# SCH_-_RC2014-_Dev_V1_1_-_freeroute.net
KiCad netlist of a schematic drawn in EasyEDA
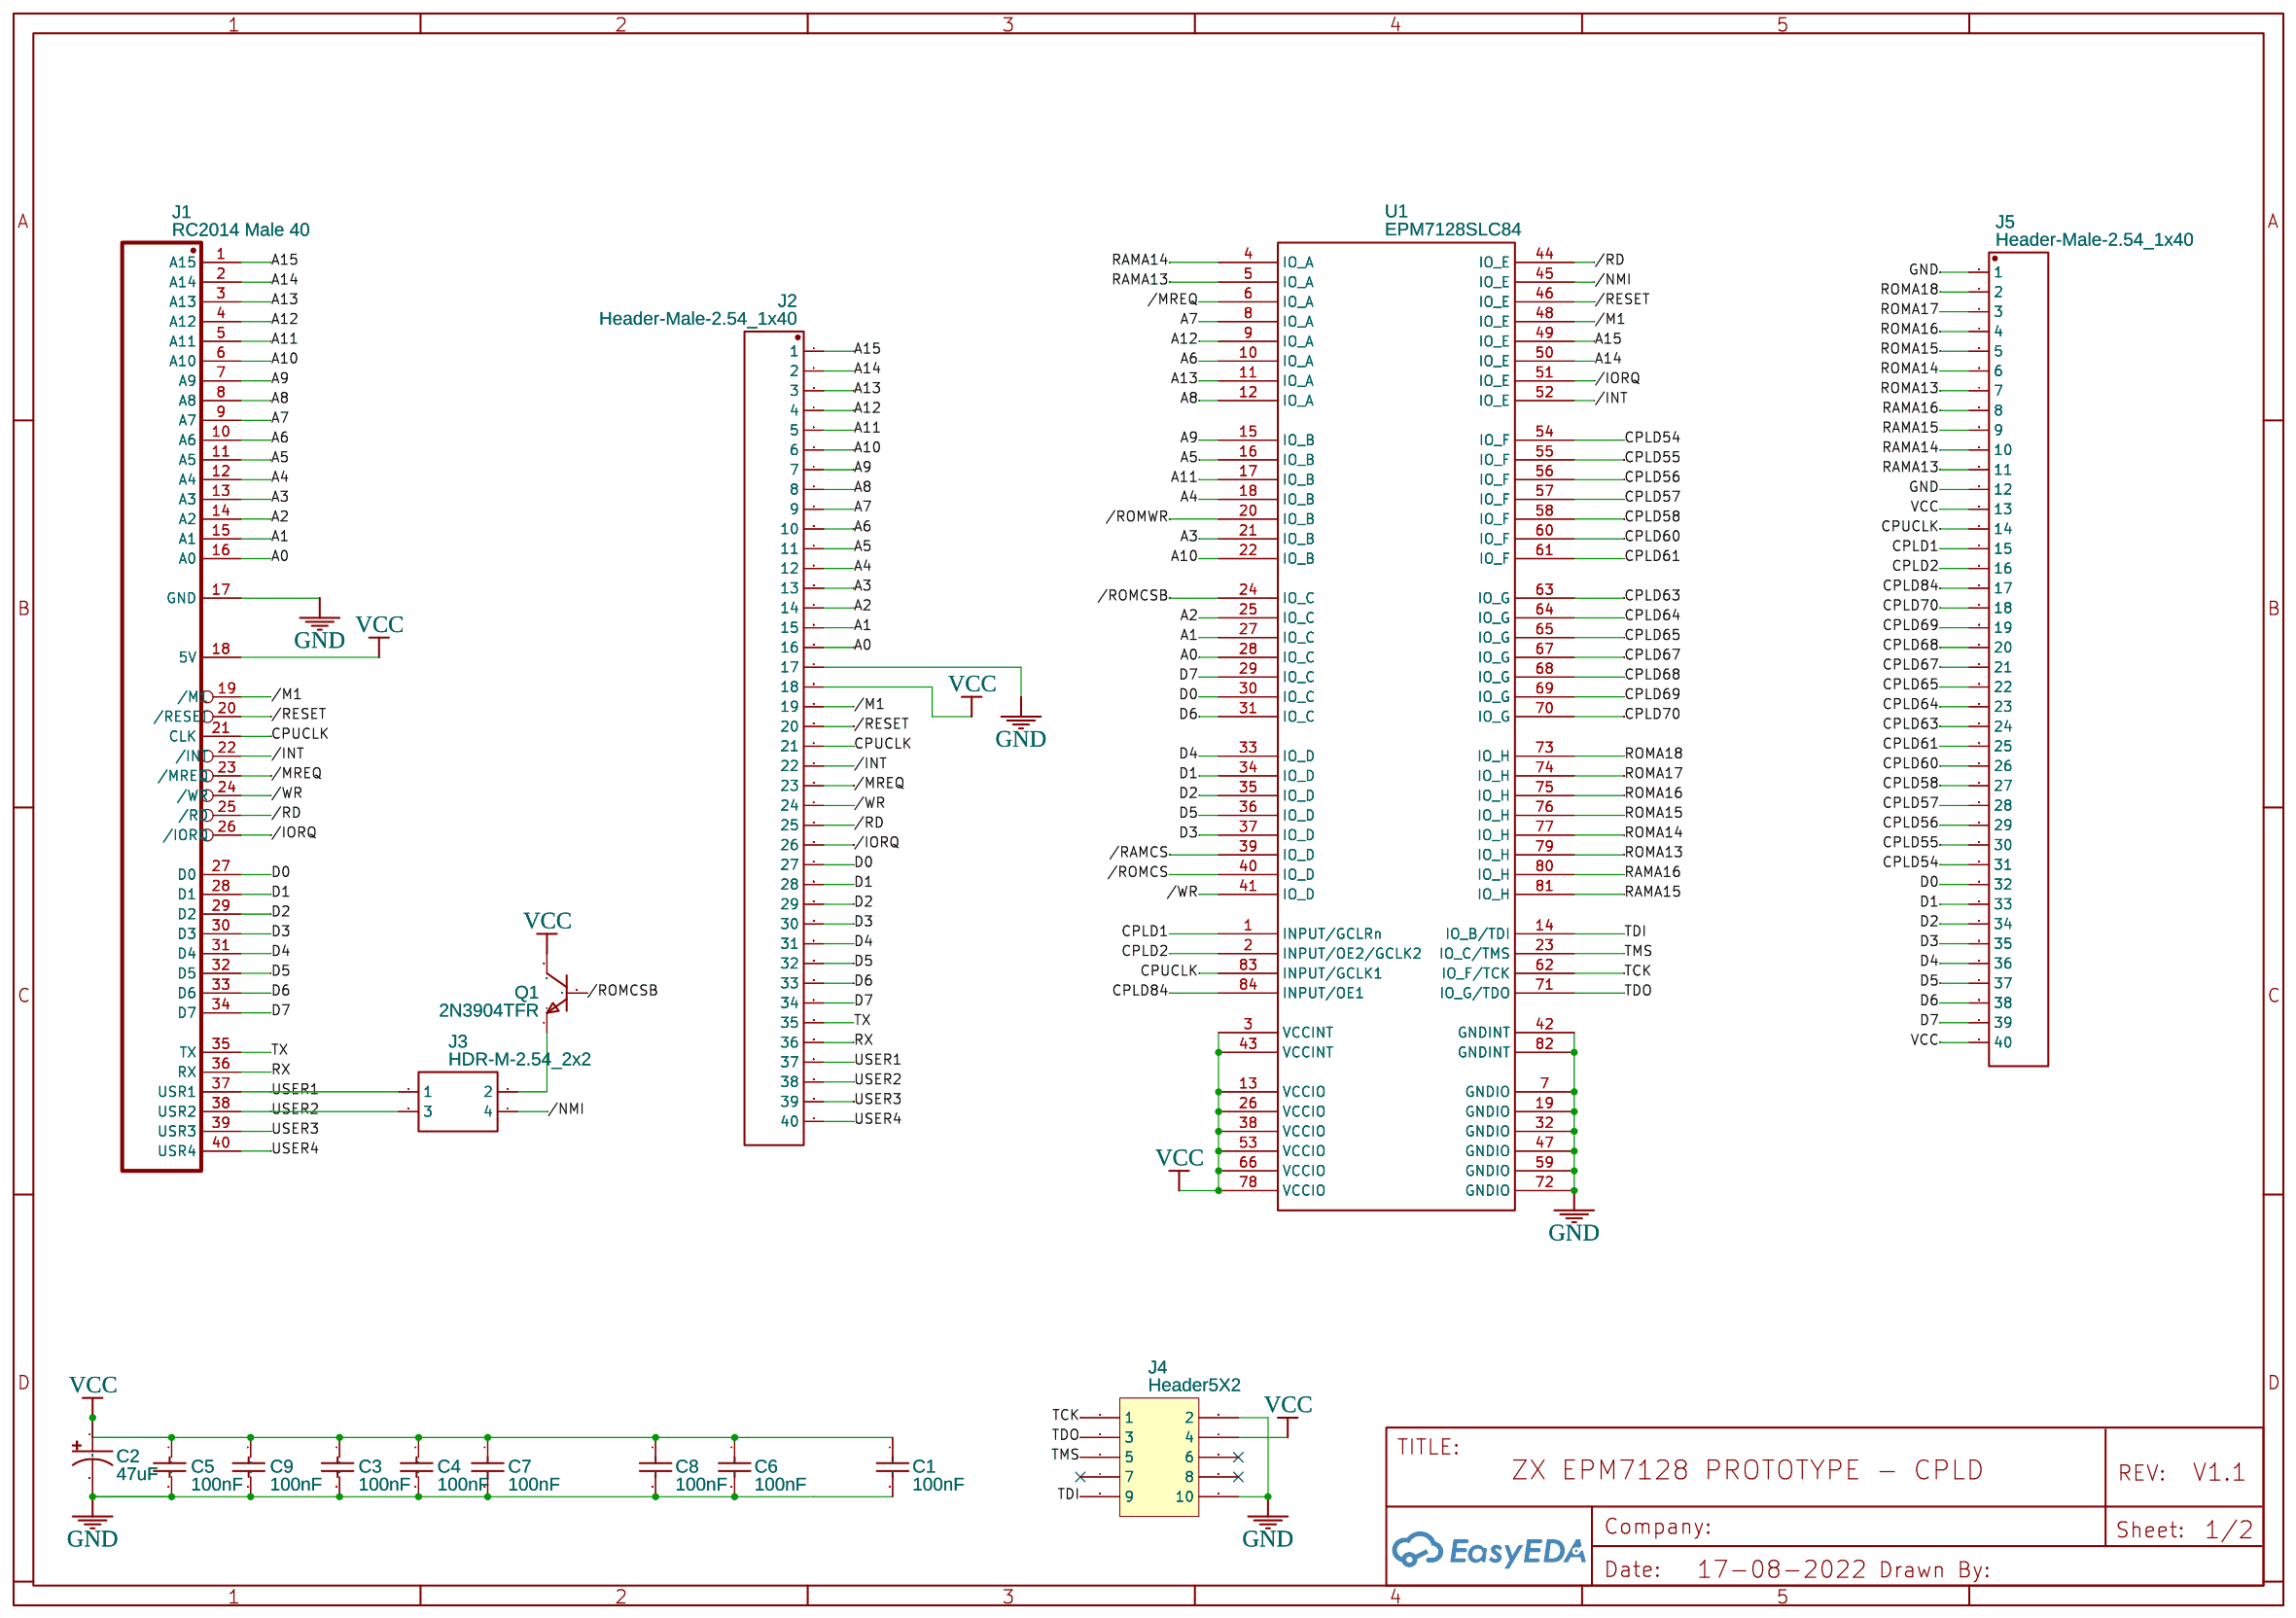
[diagram p0: SCH - RC2014 - Dev V1.1]
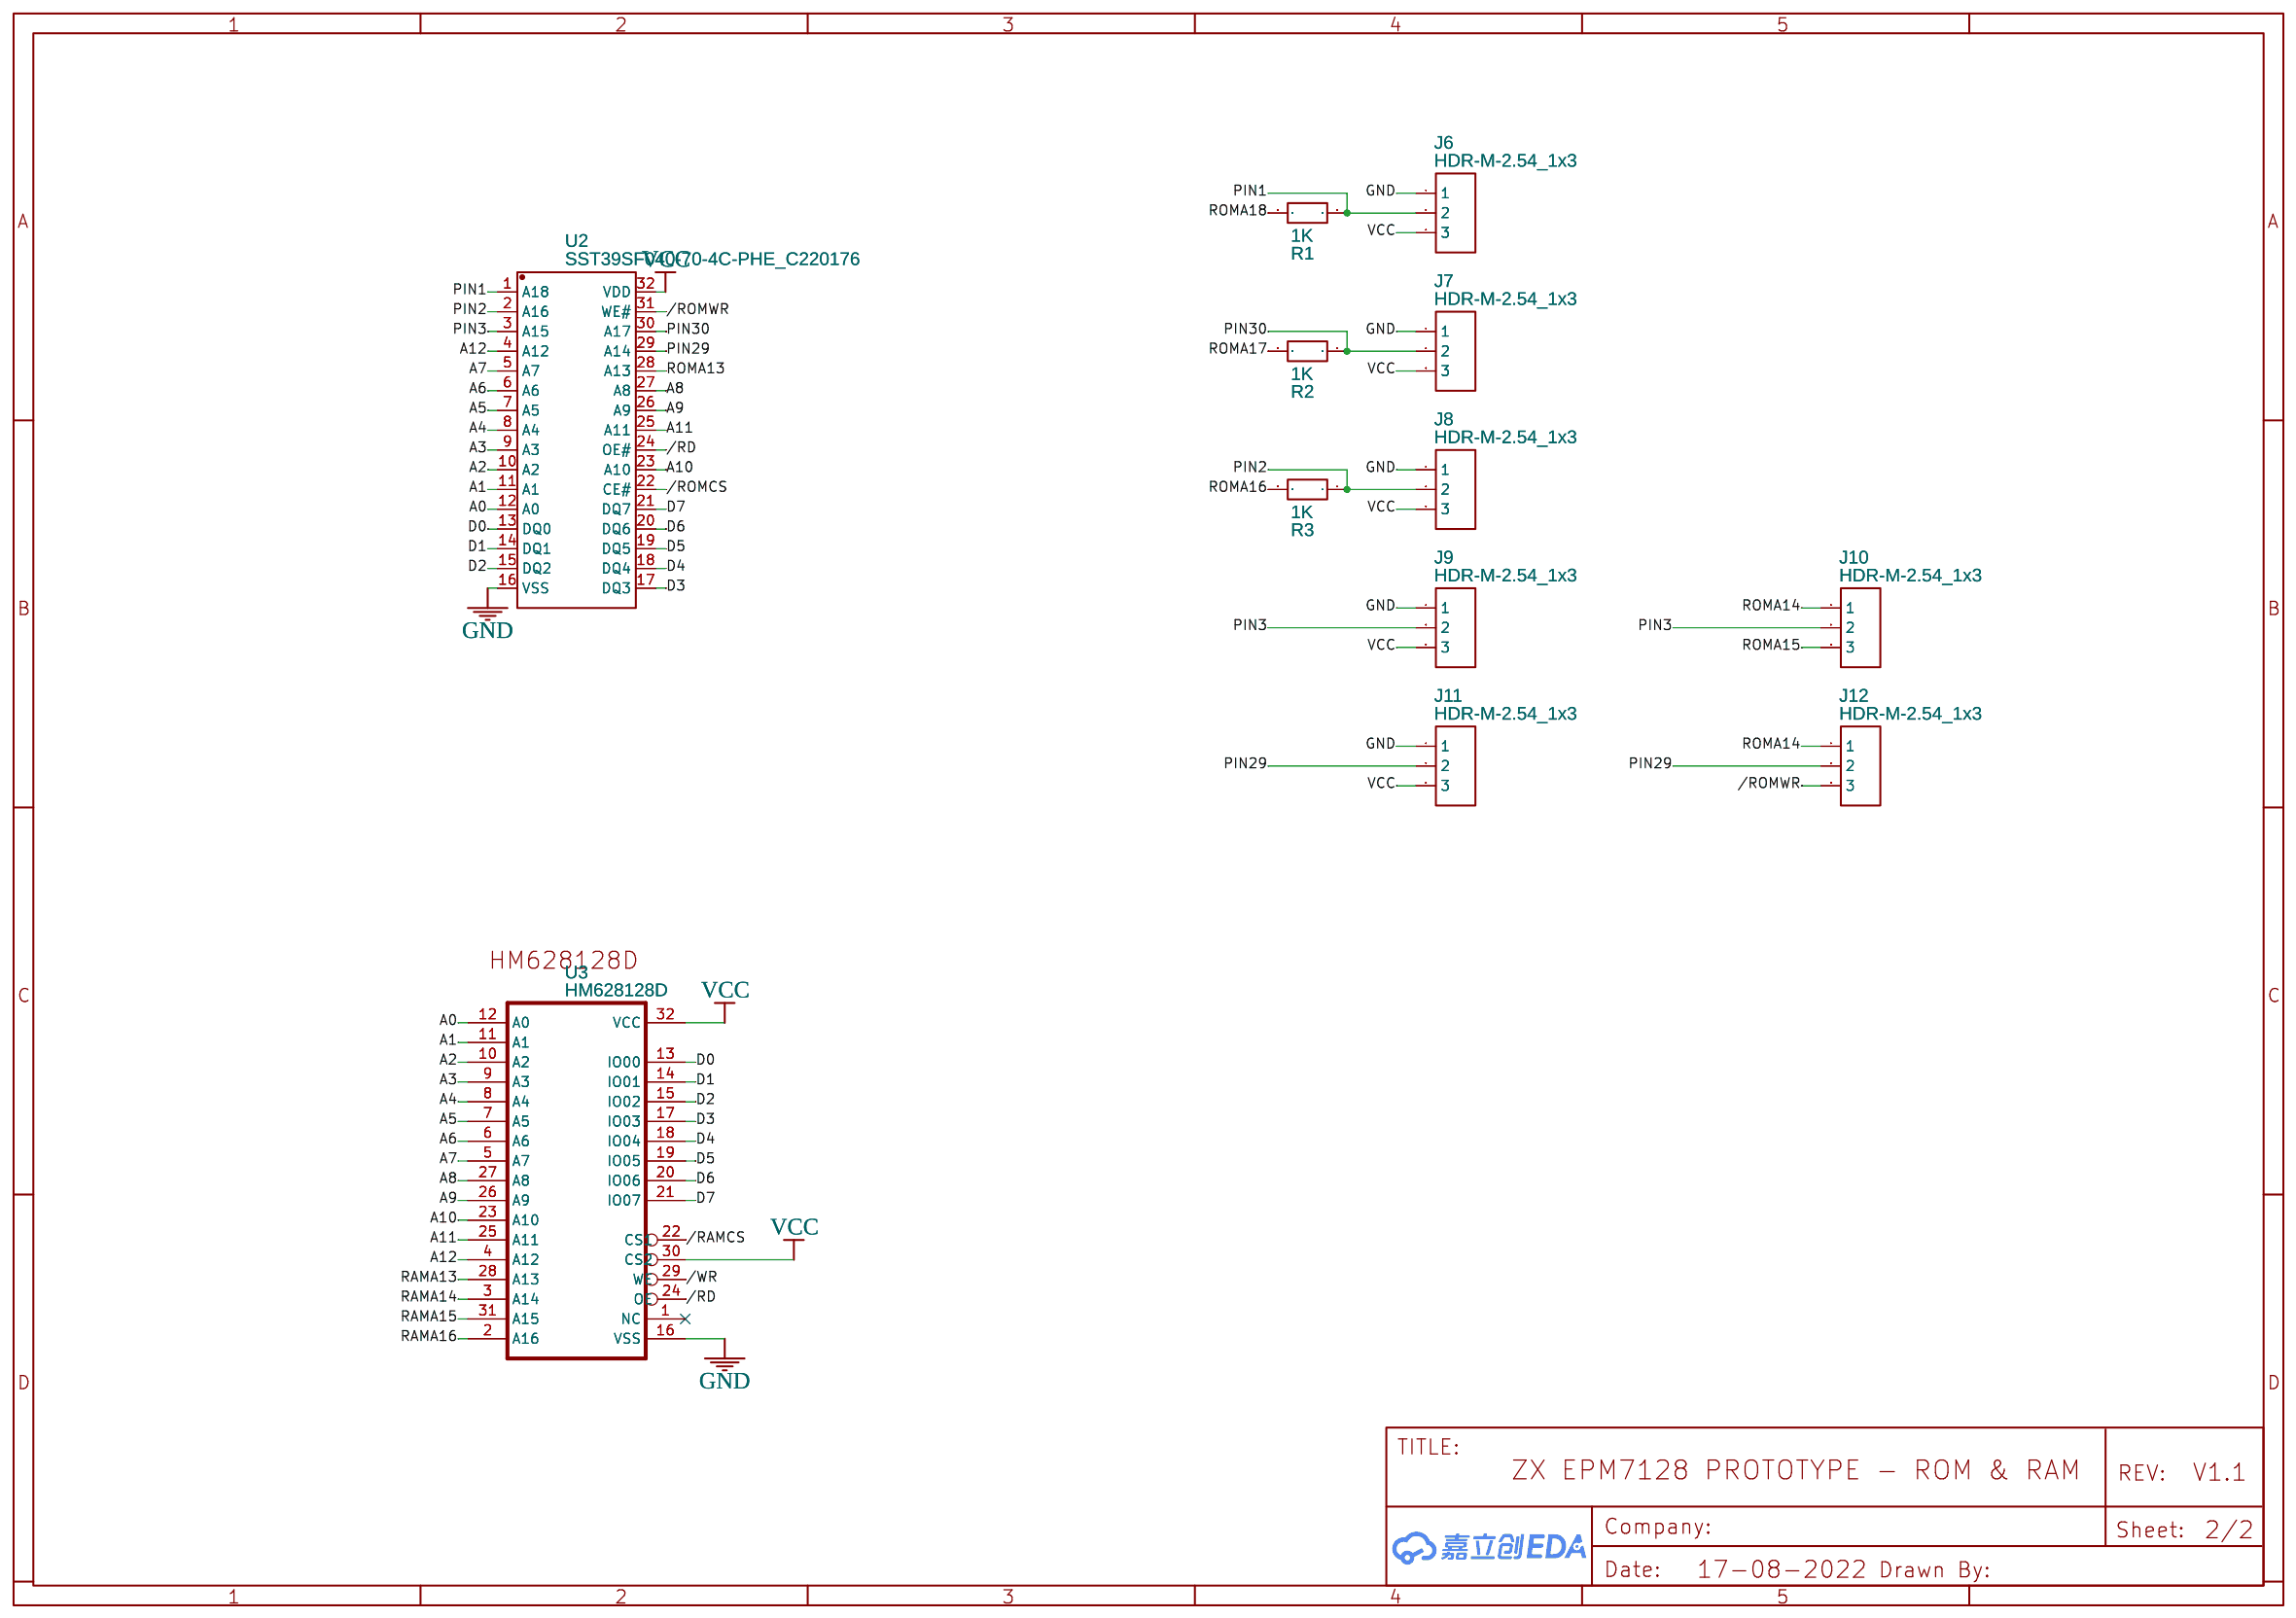
[diagram p1: SCH - ROM & RAM]

(export (version "E")
  (design (tool "Eeschema 10.0.6"))
  (components
    (comp (ref "C1")
      (value "100nF")
      (fields
        (field (name "BOM_Manufacturer Part") "100nF (104) ±20% 100V")
        (field (name "BOM_Supplier Part") "C72322")
      )
      (libsource (lib "") (part "100nF (104) ±20% 100V_1"))
    )
    (comp (ref "C2")
      (value "47uF")
      (fields
        (field (name "BOM_Manufacturer Part") "KM1H470ME110A00CV0")
        (field (name "BOM_Supplier Part") "C190654")
      )
      (libsource (lib "") (part "KM1H470ME110A00CV0"))
    )
    (comp (ref "C3")
      (value "100nF")
      (fields
        (field (name "BOM_Manufacturer Part") "100nF (104) ±20% 100V")
        (field (name "BOM_Supplier Part") "C72322")
      )
      (libsource (lib "") (part "100nF (104) ±20% 100V"))
    )
    (comp (ref "C4")
      (value "100nF")
      (fields
        (field (name "BOM_Manufacturer Part") "100nF (104) ±20% 100V")
        (field (name "BOM_Supplier Part") "C72322")
      )
      (libsource (lib "") (part "100nF (104) ±20% 100V"))
    )
    (comp (ref "C5")
      (value "100nF")
      (fields
        (field (name "BOM_Manufacturer Part") "100nF (104) ±20% 100V")
        (field (name "BOM_Supplier Part") "C72322")
      )
      (libsource (lib "") (part "100nF (104) ±20% 100V"))
    )
    (comp (ref "C6")
      (value "100nF")
      (fields
        (field (name "BOM_Manufacturer Part") "100nF (104) ±20% 100V")
        (field (name "BOM_Supplier Part") "C72322")
      )
      (libsource (lib "") (part "100nF (104) ±20% 100V_1"))
    )
    (comp (ref "C7")
      (value "100nF")
      (fields
        (field (name "BOM_Manufacturer Part") "100nF (104) ±20% 100V")
        (field (name "BOM_Supplier Part") "C72322")
      )
      (libsource (lib "") (part "100nF (104) ±20% 100V_1"))
    )
    (comp (ref "C8")
      (value "100nF")
      (fields
        (field (name "BOM_Manufacturer Part") "100nF (104) ±20% 100V")
        (field (name "BOM_Supplier Part") "C72322")
      )
      (libsource (lib "") (part "100nF (104) ±20% 100V_1"))
    )
    (comp (ref "C9")
      (value "100nF")
      (fields
        (field (name "BOM_Manufacturer Part") "100nF (104) ±20% 100V")
        (field (name "BOM_Supplier Part") "C72322")
      )
      (libsource (lib "") (part "100nF (104) ±20% 100V"))
    )
    (comp (ref "J1") (value "RC2014 Male 40") (libsource (lib "") (part "RC2014 Male 40")))
    (comp (ref "J2")
      (value "Header-Male-2.54_1x40")
      (fields
        (field (name "BOM_Manufacturer Part") "2.54mm 1x40P")
        (field (name "BOM_Supplier Part") "C2337")
      )
      (libsource (lib "") (part "Header-Male-2.54_1x40_1"))
    )
    (comp (ref "J3")
      (value "HDR-M-2.54_2x2")
      (fields (field (name "BOM_Supplier Part") "C66690"))
      (libsource (lib "") (part "HDR-M-2.54_2x2"))
    )
    (comp (ref "J4")
      (value "Header5X2")
      (fields
        (field (name "BOM_Manufacturer Part") "SBH11-PBPC-D05-ST-BK")
        (field (name "BOM_Supplier Part") "S9169-ND")
      )
      (libsource (lib "") (part "Header5X2"))
    )
    (comp (ref "J5")
      (value "Header-Male-2.54_1x40")
      (fields
        (field (name "BOM_Manufacturer Part") "2.54mm 1x40P")
        (field (name "BOM_Supplier Part") "C2337")
      )
      (libsource (lib "") (part "Header-Male-2.54_1x40"))
    )
    (comp (ref "Q1")
      (value "2N3904TFR")
      (fields (field (name "BOM_Supplier Part") "C258185"))
      (libsource (lib "") (part "2N3904TFR"))
    )
    (comp (ref "U1")
      (value "EPM7128SLC84")
      (fields (field (name "BOM_Supplier Part") "692-Z8S18020VEG"))
      (libsource (lib "") (part "EPM7128SLC84"))
    )
    (comp (ref "J6")
      (value "HDR-M-2.54_1x3")
      (fields (field (name "BOM_Supplier Part") "C180248"))
      (libsource (lib "") (part "HDR-M-2.54_1x3"))
    )
    (comp (ref "J7")
      (value "HDR-M-2.54_1x3")
      (fields (field (name "BOM_Supplier Part") "C180248"))
      (libsource (lib "") (part "HDR-M-2.54_1x3"))
    )
    (comp (ref "J8")
      (value "HDR-M-2.54_1x3")
      (fields (field (name "BOM_Supplier Part") "C180248"))
      (libsource (lib "") (part "HDR-M-2.54_1x3"))
    )
    (comp (ref "J9")
      (value "HDR-M-2.54_1x3")
      (fields (field (name "BOM_Supplier Part") "C180248"))
      (libsource (lib "") (part "HDR-M-2.54_1x3"))
    )
    (comp (ref "J10")
      (value "HDR-M-2.54_1x3")
      (fields (field (name "BOM_Supplier Part") "C180248"))
      (libsource (lib "") (part "HDR-M-2.54_1x3"))
    )
    (comp (ref "J11")
      (value "HDR-M-2.54_1x3")
      (fields (field (name "BOM_Supplier Part") "C180248"))
      (libsource (lib "") (part "HDR-M-2.54_1x3"))
    )
    (comp (ref "J12")
      (value "HDR-M-2.54_1x3")
      (fields (field (name "BOM_Supplier Part") "C180248"))
      (libsource (lib "") (part "HDR-M-2.54_1x3"))
    )
    (comp (ref "R1") (value "1K") (libsource (lib "") (part "R_AXIAL-0.3_EU")))
    (comp (ref "R2") (value "1K") (libsource (lib "") (part "R_AXIAL-0.3_EU")))
    (comp (ref "R3") (value "1K") (libsource (lib "") (part "R_AXIAL-0.3_EU")))
    (comp (ref "U2")
      (value "SST39SF040-70-4C-PHE_C220176")
      (fields
        (field (name "BOM_Manufacturer Part") "SST39SF040-70-4C-PHE")
        (field (name "BOM_Supplier Part") "C220176")
      )
      (libsource (lib "") (part "SST39SF040-70-4C-PHE_C220176"))
    )
    (comp (ref "U3") (value "HM628128D") (libsource (lib "") (part "HM628128D")))
  )
  (nets
    (net (code "1") (name "A0") (class "Default")
      (node (ref "J1") (pin "16") (pinfunction "A0_16") (pintype "unspecified"))
      (node (ref "J2") (pin "16") (pinfunction "16_16") (pintype "unspecified"))
      (node (ref "U1") (pin "28") (pinfunction "IO_C_28") (pintype "passive"))
      (node (ref "U2") (pin "12") (pinfunction "A0_12") (pintype "unspecified"))
      (node (ref "U3") (pin "12") (pinfunction "A0_12") (pintype "input"))
    )
    (net (code "2") (name "A1") (class "Default")
      (node (ref "J1") (pin "15") (pinfunction "A1_15") (pintype "unspecified"))
      (node (ref "J2") (pin "15") (pinfunction "15_15") (pintype "unspecified"))
      (node (ref "U1") (pin "27") (pinfunction "IO_C_27") (pintype "input"))
      (node (ref "U2") (pin "11") (pinfunction "A1_11") (pintype "unspecified"))
      (node (ref "U3") (pin "11") (pinfunction "A1_11") (pintype "input"))
    )
    (net (code "3") (name "A2") (class "Default")
      (node (ref "J1") (pin "14") (pinfunction "A2_14") (pintype "unspecified"))
      (node (ref "J2") (pin "14") (pinfunction "14_14") (pintype "unspecified"))
      (node (ref "U1") (pin "25") (pinfunction "IO_C_25") (pintype "bidirectional"))
      (node (ref "U2") (pin "10") (pinfunction "A2_10") (pintype "unspecified"))
      (node (ref "U3") (pin "10") (pinfunction "A2_10") (pintype "input"))
    )
    (net (code "4") (name "A3") (class "Default")
      (node (ref "J1") (pin "13") (pinfunction "A3_13") (pintype "unspecified"))
      (node (ref "J2") (pin "13") (pinfunction "13_13") (pintype "unspecified"))
      (node (ref "U1") (pin "21") (pinfunction "IO_B_21") (pintype "bidirectional"))
      (node (ref "U2") (pin "9") (pinfunction "A3_9") (pintype "unspecified"))
      (node (ref "U3") (pin "9") (pinfunction "A3_9") (pintype "input"))
    )
    (net (code "5") (name "A4") (class "Default")
      (node (ref "J1") (pin "12") (pinfunction "A4_12") (pintype "unspecified"))
      (node (ref "J2") (pin "12") (pinfunction "12_12") (pintype "unspecified"))
      (node (ref "U1") (pin "18") (pinfunction "IO_B_18") (pintype "bidirectional"))
      (node (ref "U2") (pin "8") (pinfunction "A4_8") (pintype "unspecified"))
      (node (ref "U3") (pin "8") (pinfunction "A4_8") (pintype "input"))
    )
    (net (code "6") (name "A5") (class "Default")
      (node (ref "J1") (pin "11") (pinfunction "A5_11") (pintype "unspecified"))
      (node (ref "J2") (pin "11") (pinfunction "11_11") (pintype "unspecified"))
      (node (ref "U1") (pin "16") (pinfunction "IO_B_16") (pintype "bidirectional"))
      (node (ref "U2") (pin "7") (pinfunction "A5_7") (pintype "unspecified"))
      (node (ref "U3") (pin "7") (pinfunction "A5_7") (pintype "input"))
    )
    (net (code "7") (name "A6") (class "Default")
      (node (ref "J1") (pin "10") (pinfunction "A6_10") (pintype "unspecified"))
      (node (ref "J2") (pin "10") (pinfunction "10_10") (pintype "unspecified"))
      (node (ref "U1") (pin "10") (pinfunction "IO_A_10") (pintype "bidirectional"))
      (node (ref "U2") (pin "6") (pinfunction "A6_6") (pintype "unspecified"))
      (node (ref "U3") (pin "6") (pinfunction "A6_6") (pintype "input"))
    )
    (net (code "8") (name "A7") (class "Default")
      (node (ref "J1") (pin "9") (pinfunction "A7_9") (pintype "unspecified"))
      (node (ref "J2") (pin "9") (pinfunction "9_9") (pintype "unspecified"))
      (node (ref "U1") (pin "8") (pinfunction "IO_A_8") (pintype "bidirectional"))
      (node (ref "U2") (pin "5") (pinfunction "A7_5") (pintype "unspecified"))
      (node (ref "U3") (pin "5") (pinfunction "A7_5") (pintype "input"))
    )
    (net (code "9") (name "A8") (class "Default")
      (node (ref "J1") (pin "8") (pinfunction "A8_8") (pintype "unspecified"))
      (node (ref "J2") (pin "8") (pinfunction "8_8") (pintype "unspecified"))
      (node (ref "U1") (pin "12") (pinfunction "IO_A_12") (pintype "bidirectional"))
      (node (ref "U2") (pin "27") (pinfunction "A8_27") (pintype "unspecified"))
      (node (ref "U3") (pin "27") (pinfunction "A8_27") (pintype "input"))
    )
    (net (code "10") (name "A9") (class "Default")
      (node (ref "J1") (pin "7") (pinfunction "A9_7") (pintype "unspecified"))
      (node (ref "J2") (pin "7") (pinfunction "7_7") (pintype "unspecified"))
      (node (ref "U1") (pin "15") (pinfunction "IO_B_15") (pintype "bidirectional"))
      (node (ref "U2") (pin "26") (pinfunction "A9_26") (pintype "unspecified"))
      (node (ref "U3") (pin "26") (pinfunction "A9_26") (pintype "input"))
    )
    (net (code "11") (name "A10") (class "Default")
      (node (ref "J1") (pin "6") (pinfunction "A10_6") (pintype "unspecified"))
      (node (ref "J2") (pin "6") (pinfunction "6_6") (pintype "unspecified"))
      (node (ref "U1") (pin "22") (pinfunction "IO_B_22") (pintype "output"))
      (node (ref "U2") (pin "23") (pinfunction "A10_23") (pintype "unspecified"))
      (node (ref "U3") (pin "23") (pinfunction "A10_23") (pintype "input"))
    )
    (net (code "12") (name "A11") (class "Default")
      (node (ref "J1") (pin "5") (pinfunction "A11_5") (pintype "unspecified"))
      (node (ref "J2") (pin "5") (pinfunction "5_5") (pintype "unspecified"))
      (node (ref "U1") (pin "17") (pinfunction "IO_B_17") (pintype "bidirectional"))
      (node (ref "U2") (pin "25") (pinfunction "A11_25") (pintype "unspecified"))
      (node (ref "U3") (pin "25") (pinfunction "A11_25") (pintype "input"))
    )
    (net (code "13") (name "A12") (class "Default")
      (node (ref "J1") (pin "4") (pinfunction "A12_4") (pintype "unspecified"))
      (node (ref "J2") (pin "4") (pinfunction "4_4") (pintype "unspecified"))
      (node (ref "U1") (pin "9") (pinfunction "IO_A_9") (pintype "bidirectional"))
      (node (ref "U2") (pin "4") (pinfunction "A12_4") (pintype "unspecified"))
      (node (ref "U3") (pin "4") (pinfunction "A12_4") (pintype "input"))
    )
    (net (code "14") (name "A13") (class "Default")
      (node (ref "J1") (pin "3") (pinfunction "A13_3") (pintype "unspecified"))
      (node (ref "J2") (pin "3") (pinfunction "3_3") (pintype "unspecified"))
      (node (ref "U1") (pin "11") (pinfunction "IO_A_11") (pintype "bidirectional"))
    )
    (net (code "15") (name "A14") (class "Default")
      (node (ref "J1") (pin "2") (pinfunction "A14_2") (pintype "unspecified"))
      (node (ref "J2") (pin "2") (pinfunction "2_2") (pintype "unspecified"))
      (node (ref "U1") (pin "50") (pinfunction "IO_E_50") (pintype "bidirectional"))
    )
    (net (code "16") (name "A15") (class "Default")
      (node (ref "J1") (pin "1") (pinfunction "A15_1") (pintype "unspecified"))
      (node (ref "J2") (pin "1") (pinfunction "1_1") (pintype "unspecified"))
      (node (ref "U1") (pin "49") (pinfunction "IO_E_49") (pintype "bidirectional"))
    )
    (net (code "17") (name "CPLD1") (class "Default")
      (node (ref "J5") (pin "15") (pinfunction "15_15") (pintype "unspecified"))
      (node (ref "U1") (pin "1") (pinfunction "INPUT/GCLRn_1") (pintype "input"))
    )
    (net (code "18") (name "CPLD2") (class "Default")
      (node (ref "J5") (pin "16") (pinfunction "16_16") (pintype "unspecified"))
      (node (ref "U1") (pin "2") (pinfunction "INPUT/OE2/GCLK2_2") (pintype "input"))
    )
    (net (code "19") (name "CPLD54") (class "Default")
      (node (ref "J5") (pin "31") (pinfunction "31_31") (pintype "unspecified"))
      (node (ref "U1") (pin "54") (pinfunction "IO_F_54") (pintype "bidirectional"))
    )
    (net (code "20") (name "CPLD55") (class "Default")
      (node (ref "J5") (pin "30") (pinfunction "30_30") (pintype "unspecified"))
      (node (ref "U1") (pin "55") (pinfunction "IO_F_55") (pintype "passive"))
    )
    (net (code "21") (name "CPLD56") (class "Default")
      (node (ref "J5") (pin "29") (pinfunction "29_29") (pintype "unspecified"))
      (node (ref "U1") (pin "56") (pinfunction "IO_F_56") (pintype "bidirectional"))
    )
    (net (code "22") (name "CPLD57") (class "Default")
      (node (ref "J5") (pin "28") (pinfunction "28_28") (pintype "unspecified"))
      (node (ref "U1") (pin "57") (pinfunction "IO_F_57") (pintype "bidirectional"))
    )
    (net (code "23") (name "CPLD58") (class "Default")
      (node (ref "J5") (pin "27") (pinfunction "27_27") (pintype "unspecified"))
      (node (ref "U1") (pin "58") (pinfunction "IO_F_58") (pintype "bidirectional"))
    )
    (net (code "24") (name "CPLD60") (class "Default")
      (node (ref "J5") (pin "26") (pinfunction "26_26") (pintype "unspecified"))
      (node (ref "U1") (pin "60") (pinfunction "IO_F_60") (pintype "bidirectional"))
    )
    (net (code "25") (name "CPLD61") (class "Default")
      (node (ref "J5") (pin "25") (pinfunction "25_25") (pintype "unspecified"))
      (node (ref "U1") (pin "61") (pinfunction "IO_F_61") (pintype "bidirectional"))
    )
    (net (code "26") (name "CPLD63") (class "Default")
      (node (ref "J5") (pin "24") (pinfunction "24_24") (pintype "unspecified"))
      (node (ref "U1") (pin "63") (pinfunction "IO_G_63") (pintype "bidirectional"))
    )
    (net (code "27") (name "CPLD64") (class "Default")
      (node (ref "J5") (pin "23") (pinfunction "23_23") (pintype "unspecified"))
      (node (ref "U1") (pin "64") (pinfunction "IO_G_64") (pintype "bidirectional"))
    )
    (net (code "28") (name "CPLD65") (class "Default")
      (node (ref "J5") (pin "22") (pinfunction "22_22") (pintype "unspecified"))
      (node (ref "U1") (pin "65") (pinfunction "IO_G_65") (pintype "passive"))
    )
    (net (code "29") (name "CPLD67") (class "Default")
      (node (ref "J5") (pin "21") (pinfunction "21_21") (pintype "unspecified"))
      (node (ref "U1") (pin "67") (pinfunction "IO_G_67") (pintype "bidirectional"))
    )
    (net (code "30") (name "CPLD68") (class "Default")
      (node (ref "J5") (pin "20") (pinfunction "20_20") (pintype "unspecified"))
      (node (ref "U1") (pin "68") (pinfunction "IO_G_68") (pintype "bidirectional"))
    )
    (net (code "31") (name "CPLD69") (class "Default")
      (node (ref "J5") (pin "19") (pinfunction "19_19") (pintype "unspecified"))
      (node (ref "U1") (pin "69") (pinfunction "IO_G_69") (pintype "passive"))
    )
    (net (code "32") (name "CPLD70") (class "Default")
      (node (ref "J5") (pin "18") (pinfunction "18_18") (pintype "unspecified"))
      (node (ref "U1") (pin "70") (pinfunction "IO_G_70") (pintype "bidirectional"))
    )
    (net (code "33") (name "CPLD84") (class "Default")
      (node (ref "J5") (pin "17") (pinfunction "17_17") (pintype "unspecified"))
      (node (ref "U1") (pin "84") (pinfunction "INPUT/OE1_84") (pintype "input"))
    )
    (net (code "34") (name "CPUCLK") (class "Default")
      (node (ref "J1") (pin "21") (pinfunction "CLK_21") (pintype "unspecified"))
      (node (ref "J2") (pin "21") (pinfunction "21_21") (pintype "unspecified"))
      (node (ref "J5") (pin "14") (pinfunction "14_14") (pintype "unspecified"))
      (node (ref "U1") (pin "83") (pinfunction "INPUT/GCLK1_83") (pintype "input"))
    )
    (net (code "35") (name "D0") (class "Default")
      (node (ref "J1") (pin "27") (pinfunction "D0_27") (pintype "unspecified"))
      (node (ref "J2") (pin "27") (pinfunction "27_27") (pintype "unspecified"))
      (node (ref "J5") (pin "32") (pinfunction "32_32") (pintype "unspecified"))
      (node (ref "U1") (pin "30") (pinfunction "IO_C_30") (pintype "bidirectional"))
      (node (ref "U2") (pin "13") (pinfunction "DQ0_13") (pintype "unspecified"))
      (node (ref "U3") (pin "13") (pinfunction "IO00_13") (pintype "unspecified"))
    )
    (net (code "36") (name "D1") (class "Default")
      (node (ref "J1") (pin "28") (pinfunction "D1_28") (pintype "unspecified"))
      (node (ref "J2") (pin "28") (pinfunction "28_28") (pintype "unspecified"))
      (node (ref "J5") (pin "33") (pinfunction "33_33") (pintype "unspecified"))
      (node (ref "U1") (pin "34") (pinfunction "IO_D_34") (pintype "input"))
      (node (ref "U2") (pin "14") (pinfunction "DQ1_14") (pintype "unspecified"))
      (node (ref "U3") (pin "14") (pinfunction "IO01_14") (pintype "unspecified"))
    )
    (net (code "37") (name "D2") (class "Default")
      (node (ref "J1") (pin "29") (pinfunction "D2_29") (pintype "unspecified"))
      (node (ref "J2") (pin "29") (pinfunction "29_29") (pintype "unspecified"))
      (node (ref "J5") (pin "34") (pinfunction "34_34") (pintype "unspecified"))
      (node (ref "U1") (pin "35") (pinfunction "IO_D_35") (pintype "input"))
      (node (ref "U2") (pin "15") (pinfunction "DQ2_15") (pintype "unspecified"))
      (node (ref "U3") (pin "15") (pinfunction "IO02_15") (pintype "unspecified"))
    )
    (net (code "38") (name "D3") (class "Default")
      (node (ref "J1") (pin "30") (pinfunction "D3_30") (pintype "unspecified"))
      (node (ref "J2") (pin "30") (pinfunction "30_30") (pintype "unspecified"))
      (node (ref "J5") (pin "35") (pinfunction "35_35") (pintype "unspecified"))
      (node (ref "U1") (pin "37") (pinfunction "IO_D_37") (pintype "bidirectional"))
      (node (ref "U2") (pin "17") (pinfunction "DQ3_17") (pintype "unspecified"))
      (node (ref "U3") (pin "17") (pinfunction "IO03_17") (pintype "unspecified"))
    )
    (net (code "39") (name "D4") (class "Default")
      (node (ref "J1") (pin "31") (pinfunction "D4_31") (pintype "unspecified"))
      (node (ref "J2") (pin "31") (pinfunction "31_31") (pintype "unspecified"))
      (node (ref "J5") (pin "36") (pinfunction "36_36") (pintype "unspecified"))
      (node (ref "U1") (pin "33") (pinfunction "IO_D_33") (pintype "bidirectional"))
      (node (ref "U2") (pin "18") (pinfunction "DQ4_18") (pintype "unspecified"))
      (node (ref "U3") (pin "18") (pinfunction "IO04_18") (pintype "unspecified"))
    )
    (net (code "40") (name "D5") (class "Default")
      (node (ref "J1") (pin "32") (pinfunction "D5_32") (pintype "unspecified"))
      (node (ref "J2") (pin "32") (pinfunction "32_32") (pintype "unspecified"))
      (node (ref "J5") (pin "37") (pinfunction "37_37") (pintype "unspecified"))
      (node (ref "U1") (pin "36") (pinfunction "IO_D_36") (pintype "bidirectional"))
      (node (ref "U2") (pin "19") (pinfunction "DQ5_19") (pintype "unspecified"))
      (node (ref "U3") (pin "19") (pinfunction "IO05_19") (pintype "unspecified"))
    )
    (net (code "41") (name "D6") (class "Default")
      (node (ref "J1") (pin "33") (pinfunction "D6_33") (pintype "unspecified"))
      (node (ref "J2") (pin "33") (pinfunction "33_33") (pintype "unspecified"))
      (node (ref "J5") (pin "38") (pinfunction "38_38") (pintype "unspecified"))
      (node (ref "U1") (pin "31") (pinfunction "IO_C_31") (pintype "passive"))
      (node (ref "U2") (pin "20") (pinfunction "DQ6_20") (pintype "unspecified"))
      (node (ref "U3") (pin "20") (pinfunction "IO06_20") (pintype "unspecified"))
    )
    (net (code "42") (name "D7") (class "Default")
      (node (ref "J1") (pin "34") (pinfunction "D7_34") (pintype "unspecified"))
      (node (ref "J2") (pin "34") (pinfunction "34_34") (pintype "unspecified"))
      (node (ref "J5") (pin "39") (pinfunction "39_39") (pintype "unspecified"))
      (node (ref "U1") (pin "29") (pinfunction "IO_C_29") (pintype "input"))
      (node (ref "U2") (pin "21") (pinfunction "DQ7_21") (pintype "unspecified"))
      (node (ref "U3") (pin "21") (pinfunction "IO07_21") (pintype "unspecified"))
    )
    (net (code "43") (name "GND") (class "Default")
      (node (ref "C1") (pin "2") (pinfunction "2_2") (pintype "input"))
      (node (ref "C2") (pin "2") (pinfunction "2_2") (pintype "unspecified"))
      (node (ref "C3") (pin "2") (pinfunction "2_2") (pintype "input"))
      (node (ref "C4") (pin "2") (pinfunction "2_2") (pintype "input"))
      (node (ref "C5") (pin "2") (pinfunction "2_2") (pintype "input"))
      (node (ref "C6") (pin "2") (pinfunction "2_2") (pintype "input"))
      (node (ref "C7") (pin "2") (pinfunction "2_2") (pintype "input"))
      (node (ref "C8") (pin "2") (pinfunction "2_2") (pintype "input"))
      (node (ref "C9") (pin "2") (pinfunction "2_2") (pintype "input"))
      (node (ref "J1") (pin "17") (pinfunction "GND_17") (pintype "unspecified"))
      (node (ref "J11") (pin "1") (pinfunction "1_1") (pintype "input"))
      (node (ref "J2") (pin "17") (pinfunction "17_17") (pintype "unspecified"))
      (node (ref "J4") (pin "10") (pinfunction "10_10") (pintype "unspecified"))
      (node (ref "J4") (pin "2") (pinfunction "2_2") (pintype "unspecified"))
      (node (ref "J5") (pin "1") (pinfunction "1_1") (pintype "unspecified"))
      (node (ref "J5") (pin "12") (pinfunction "12_12") (pintype "unspecified"))
      (node (ref "J6") (pin "1") (pinfunction "1_1") (pintype "input"))
      (node (ref "J7") (pin "1") (pinfunction "1_1") (pintype "input"))
      (node (ref "J8") (pin "1") (pinfunction "1_1") (pintype "input"))
      (node (ref "J9") (pin "1") (pinfunction "1_1") (pintype "input"))
      (node (ref "U1") (pin "19") (pinfunction "GNDIO_19") (pintype "bidirectional"))
      (node (ref "U1") (pin "32") (pinfunction "GNDIO_32") (pintype "bidirectional"))
      (node (ref "U1") (pin "42") (pinfunction "GNDINT_42") (pintype "input"))
      (node (ref "U1") (pin "47") (pinfunction "GNDIO_47") (pintype "bidirectional"))
      (node (ref "U1") (pin "59") (pinfunction "GNDIO_59") (pintype "bidirectional"))
      (node (ref "U1") (pin "7") (pinfunction "GNDIO_7") (pintype "bidirectional"))
      (node (ref "U1") (pin "72") (pinfunction "GNDIO_72") (pintype "bidirectional"))
      (node (ref "U1") (pin "82") (pinfunction "GNDINT_82") (pintype "input"))
      (node (ref "U2") (pin "16") (pinfunction "VSS_16") (pintype "unspecified"))
      (node (ref "U3") (pin "16") (pinfunction "VSS_16") (pintype "passive"))
    )
    (net (code "44") (name "Net-(Q1-E)") (class "Default")
      (node (ref "J3") (pin "2") (pinfunction "2_2") (pintype "input"))
      (node (ref "Q1") (pin "1") (pinfunction "E_1") (pintype "unspecified"))
    )
    (net (code "45") (name "PIN1") (class "Default")
      (node (ref "J6") (pin "2") (pinfunction "2_2") (pintype "input"))
      (node (ref "R1") (pin "1") (pinfunction "1_1") (pintype "unspecified"))
      (node (ref "U2") (pin "1") (pinfunction "A18_1") (pintype "unspecified"))
    )
    (net (code "46") (name "PIN2") (class "Default")
      (node (ref "J8") (pin "2") (pinfunction "2_2") (pintype "input"))
      (node (ref "R3") (pin "1") (pinfunction "1_1") (pintype "unspecified"))
      (node (ref "U2") (pin "2") (pinfunction "A16_2") (pintype "unspecified"))
    )
    (net (code "47") (name "PIN3") (class "Default")
      (node (ref "J10") (pin "2") (pinfunction "2_2") (pintype "input"))
      (node (ref "J9") (pin "2") (pinfunction "2_2") (pintype "input"))
      (node (ref "U2") (pin "3") (pinfunction "A15_3") (pintype "unspecified"))
    )
    (net (code "48") (name "PIN29") (class "Default")
      (node (ref "J11") (pin "2") (pinfunction "2_2") (pintype "input"))
      (node (ref "J12") (pin "2") (pinfunction "2_2") (pintype "input"))
      (node (ref "U2") (pin "29") (pinfunction "A14_29") (pintype "unspecified"))
    )
    (net (code "49") (name "PIN30") (class "Default")
      (node (ref "J7") (pin "2") (pinfunction "2_2") (pintype "input"))
      (node (ref "R2") (pin "1") (pinfunction "1_1") (pintype "unspecified"))
      (node (ref "U2") (pin "30") (pinfunction "A17_30") (pintype "unspecified"))
    )
    (net (code "50") (name "RAMA13") (class "Default")
      (node (ref "J5") (pin "11") (pinfunction "11_11") (pintype "unspecified"))
      (node (ref "U1") (pin "5") (pinfunction "IO_A_5") (pintype "bidirectional"))
      (node (ref "U3") (pin "28") (pinfunction "A13_28") (pintype "input"))
    )
    (net (code "51") (name "RAMA14") (class "Default")
      (node (ref "J5") (pin "10") (pinfunction "10_10") (pintype "unspecified"))
      (node (ref "U1") (pin "4") (pinfunction "IO_A_4") (pintype "bidirectional"))
      (node (ref "U3") (pin "3") (pinfunction "A14_3") (pintype "input"))
    )
    (net (code "52") (name "RAMA15") (class "Default")
      (node (ref "J5") (pin "9") (pinfunction "9_9") (pintype "unspecified"))
      (node (ref "U1") (pin "81") (pinfunction "IO_H_81") (pintype "bidirectional"))
      (node (ref "U3") (pin "31") (pinfunction "A15_31") (pintype "input"))
    )
    (net (code "53") (name "RAMA16") (class "Default")
      (node (ref "J5") (pin "8") (pinfunction "8_8") (pintype "unspecified"))
      (node (ref "U1") (pin "80") (pinfunction "IO_H_80") (pintype "bidirectional"))
      (node (ref "U3") (pin "2") (pinfunction "A16_2") (pintype "input"))
    )
    (net (code "54") (name "ROMA13") (class "Default")
      (node (ref "J5") (pin "7") (pinfunction "7_7") (pintype "unspecified"))
      (node (ref "U1") (pin "79") (pinfunction "IO_H_79") (pintype "bidirectional"))
      (node (ref "U2") (pin "28") (pinfunction "A13_28") (pintype "unspecified"))
    )
    (net (code "55") (name "ROMA14") (class "Default")
      (node (ref "J10") (pin "1") (pinfunction "1_1") (pintype "input"))
      (node (ref "J12") (pin "1") (pinfunction "1_1") (pintype "input"))
      (node (ref "J5") (pin "6") (pinfunction "6_6") (pintype "unspecified"))
      (node (ref "U1") (pin "77") (pinfunction "IO_H_77") (pintype "bidirectional"))
    )
    (net (code "56") (name "ROMA15") (class "Default")
      (node (ref "J10") (pin "3") (pinfunction "3_3") (pintype "input"))
      (node (ref "J5") (pin "5") (pinfunction "5_5") (pintype "unspecified"))
      (node (ref "U1") (pin "76") (pinfunction "IO_H_76") (pintype "bidirectional"))
    )
    (net (code "57") (name "ROMA16") (class "Default")
      (node (ref "J5") (pin "4") (pinfunction "4_4") (pintype "unspecified"))
      (node (ref "R3") (pin "2") (pinfunction "2_2") (pintype "unspecified"))
      (node (ref "U1") (pin "75") (pinfunction "IO_H_75") (pintype "bidirectional"))
    )
    (net (code "58") (name "ROMA17") (class "Default")
      (node (ref "J5") (pin "3") (pinfunction "3_3") (pintype "unspecified"))
      (node (ref "R2") (pin "2") (pinfunction "2_2") (pintype "unspecified"))
      (node (ref "U1") (pin "74") (pinfunction "IO_H_74") (pintype "bidirectional"))
    )
    (net (code "59") (name "ROMA18") (class "Default")
      (node (ref "J5") (pin "2") (pinfunction "2_2") (pintype "unspecified"))
      (node (ref "R1") (pin "2") (pinfunction "2_2") (pintype "unspecified"))
      (node (ref "U1") (pin "73") (pinfunction "IO_H_73") (pintype "bidirectional"))
    )
    (net (code "60") (name "RX") (class "Default")
      (node (ref "J1") (pin "36") (pinfunction "RX_36") (pintype "unspecified"))
      (node (ref "J2") (pin "36") (pinfunction "36_36") (pintype "unspecified"))
    )
    (net (code "61") (name "TCK") (class "Default")
      (node (ref "J4") (pin "1") (pinfunction "1_1") (pintype "unspecified"))
      (node (ref "U1") (pin "62") (pinfunction "IO_F/TCK_62") (pintype "bidirectional"))
    )
    (net (code "62") (name "TDI") (class "Default")
      (node (ref "J4") (pin "9") (pinfunction "9_9") (pintype "unspecified"))
      (node (ref "U1") (pin "14") (pinfunction "IO_B/TDI_14") (pintype "bidirectional"))
    )
    (net (code "63") (name "TDO") (class "Default")
      (node (ref "J4") (pin "3") (pinfunction "3_3") (pintype "unspecified"))
      (node (ref "U1") (pin "71") (pinfunction "IO_G/TDO_71") (pintype "bidirectional"))
    )
    (net (code "64") (name "TMS") (class "Default")
      (node (ref "J4") (pin "5") (pinfunction "5_5") (pintype "unspecified"))
      (node (ref "U1") (pin "23") (pinfunction "IO_C/TMS_23") (pintype "bidirectional"))
    )
    (net (code "65") (name "TX") (class "Default")
      (node (ref "J1") (pin "35") (pinfunction "TX_35") (pintype "unspecified"))
      (node (ref "J2") (pin "35") (pinfunction "35_35") (pintype "unspecified"))
    )
    (net (code "66") (name "USER1") (class "Default")
      (node (ref "J1") (pin "37") (pinfunction "USR1_37") (pintype "unspecified"))
      (node (ref "J2") (pin "37") (pinfunction "37_37") (pintype "unspecified"))
      (node (ref "J3") (pin "1") (pinfunction "1_1") (pintype "input"))
    )
    (net (code "67") (name "USER2") (class "Default")
      (node (ref "J1") (pin "38") (pinfunction "USR2_38") (pintype "unspecified"))
      (node (ref "J2") (pin "38") (pinfunction "38_38") (pintype "unspecified"))
      (node (ref "J3") (pin "3") (pinfunction "3_3") (pintype "input"))
    )
    (net (code "68") (name "USER3") (class "Default")
      (node (ref "J1") (pin "39") (pinfunction "USR3_39") (pintype "unspecified"))
      (node (ref "J2") (pin "39") (pinfunction "39_39") (pintype "unspecified"))
    )
    (net (code "69") (name "USER4") (class "Default")
      (node (ref "J1") (pin "40") (pinfunction "USR4_40") (pintype "unspecified"))
      (node (ref "J2") (pin "40") (pinfunction "40_40") (pintype "unspecified"))
    )
    (net (code "70") (name "VCC") (class "Default")
      (node (ref "C1") (pin "1") (pinfunction "1_1") (pintype "input"))
      (node (ref "C2") (pin "1") (pinfunction "1_1") (pintype "unspecified"))
      (node (ref "C3") (pin "1") (pinfunction "1_1") (pintype "input"))
      (node (ref "C4") (pin "1") (pinfunction "1_1") (pintype "input"))
      (node (ref "C5") (pin "1") (pinfunction "1_1") (pintype "input"))
      (node (ref "C6") (pin "1") (pinfunction "1_1") (pintype "input"))
      (node (ref "C7") (pin "1") (pinfunction "1_1") (pintype "input"))
      (node (ref "C8") (pin "1") (pinfunction "1_1") (pintype "input"))
      (node (ref "C9") (pin "1") (pinfunction "1_1") (pintype "input"))
      (node (ref "J1") (pin "18") (pinfunction "5V_18") (pintype "unspecified"))
      (node (ref "J11") (pin "3") (pinfunction "3_3") (pintype "input"))
      (node (ref "J2") (pin "18") (pinfunction "18_18") (pintype "unspecified"))
      (node (ref "J4") (pin "4") (pinfunction "4_4") (pintype "unspecified"))
      (node (ref "J5") (pin "13") (pinfunction "13_13") (pintype "unspecified"))
      (node (ref "J5") (pin "40") (pinfunction "40_40") (pintype "unspecified"))
      (node (ref "J6") (pin "3") (pinfunction "3_3") (pintype "input"))
      (node (ref "J7") (pin "3") (pinfunction "3_3") (pintype "input"))
      (node (ref "J8") (pin "3") (pinfunction "3_3") (pintype "input"))
      (node (ref "J9") (pin "3") (pinfunction "3_3") (pintype "input"))
      (node (ref "Q1") (pin "3") (pinfunction "C_3") (pintype "unspecified"))
      (node (ref "U1") (pin "13") (pinfunction "VCCIO_13") (pintype "bidirectional"))
      (node (ref "U1") (pin "26") (pinfunction "VCCIO_26") (pintype "bidirectional"))
      (node (ref "U1") (pin "3") (pinfunction "VCCINT_3") (pintype "bidirectional"))
      (node (ref "U1") (pin "38") (pinfunction "VCCIO_38") (pintype "bidirectional"))
      (node (ref "U1") (pin "43") (pinfunction "VCCINT_43") (pintype "bidirectional"))
      (node (ref "U1") (pin "53") (pinfunction "VCCIO_53") (pintype "bidirectional"))
      (node (ref "U1") (pin "66") (pinfunction "VCCIO_66") (pintype "bidirectional"))
      (node (ref "U1") (pin "78") (pinfunction "VCCIO_78") (pintype "bidirectional"))
      (node (ref "U2") (pin "32") (pinfunction "VDD_32") (pintype "unspecified"))
      (node (ref "U3") (pin "30") (pinfunction "CS2_30") (pintype "input"))
      (node (ref "U3") (pin "32") (pinfunction "VCC_32") (pintype "passive"))
    )
    (net (code "71") (name "unconnected-(J4-Pad6)") (class "Default")
      (node (ref "J4") (pin "6") (pinfunction "6_6") (pintype "unspecified+no_connect"))
    )
    (net (code "72") (name "unconnected-(J4-Pad7)") (class "Default")
      (node (ref "J4") (pin "7") (pinfunction "7_7") (pintype "unspecified+no_connect"))
    )
    (net (code "73") (name "unconnected-(J4-Pad8)") (class "Default")
      (node (ref "J4") (pin "8") (pinfunction "8_8") (pintype "unspecified+no_connect"))
    )
    (net (code "74") (name "unconnected-(U3-NC-Pad1)") (class "Default")
      (node (ref "U3") (pin "1") (pinfunction "NC_1") (pintype "unspecified+no_connect"))
    )
    (net (code "75") (name "{slash}INT") (class "Default")
      (node (ref "J1") (pin "22") (pinfunction "/INT_22") (pintype "unspecified"))
      (node (ref "J2") (pin "22") (pinfunction "22_22") (pintype "unspecified"))
      (node (ref "U1") (pin "52") (pinfunction "IO_E_52") (pintype "bidirectional"))
    )
    (net (code "76") (name "{slash}IORQ") (class "Default")
      (node (ref "J1") (pin "26") (pinfunction "/IORQ_26") (pintype "unspecified"))
      (node (ref "J2") (pin "26") (pinfunction "26_26") (pintype "unspecified"))
      (node (ref "U1") (pin "51") (pinfunction "IO_E_51") (pintype "passive"))
    )
    (net (code "77") (name "{slash}M1") (class "Default")
      (node (ref "J1") (pin "19") (pinfunction "/M1_19") (pintype "unspecified"))
      (node (ref "J2") (pin "19") (pinfunction "19_19") (pintype "unspecified"))
      (node (ref "U1") (pin "48") (pinfunction "IO_E_48") (pintype "bidirectional"))
    )
    (net (code "78") (name "{slash}MREQ") (class "Default")
      (node (ref "J1") (pin "23") (pinfunction "/MREQ_23") (pintype "unspecified"))
      (node (ref "J2") (pin "23") (pinfunction "23_23") (pintype "unspecified"))
      (node (ref "U1") (pin "6") (pinfunction "IO_A_6") (pintype "bidirectional"))
    )
    (net (code "79") (name "{slash}NMI") (class "Default")
      (node (ref "J3") (pin "4") (pinfunction "4_4") (pintype "input"))
      (node (ref "U1") (pin "45") (pinfunction "IO_E_45") (pintype "bidirectional"))
    )
    (net (code "80") (name "{slash}RAMCS") (class "Default")
      (node (ref "U1") (pin "39") (pinfunction "IO_D_39") (pintype "bidirectional"))
      (node (ref "U3") (pin "22") (pinfunction "CS1_22") (pintype "input"))
    )
    (net (code "81") (name "{slash}RD") (class "Default")
      (node (ref "J1") (pin "25") (pinfunction "/RD_25") (pintype "unspecified"))
      (node (ref "J2") (pin "25") (pinfunction "25_25") (pintype "unspecified"))
      (node (ref "U1") (pin "44") (pinfunction "IO_E_44") (pintype "bidirectional"))
      (node (ref "U2") (pin "24") (pinfunction "OE#_24") (pintype "unspecified"))
      (node (ref "U3") (pin "24") (pinfunction "OE_24") (pintype "input"))
    )
    (net (code "82") (name "{slash}RESET") (class "Default")
      (node (ref "J1") (pin "20") (pinfunction "/RESET_20") (pintype "unspecified"))
      (node (ref "J2") (pin "20") (pinfunction "20_20") (pintype "unspecified"))
      (node (ref "U1") (pin "46") (pinfunction "IO_E_46") (pintype "bidirectional"))
    )
    (net (code "83") (name "{slash}ROMCS") (class "Default")
      (node (ref "U1") (pin "40") (pinfunction "IO_D_40") (pintype "bidirectional"))
      (node (ref "U2") (pin "22") (pinfunction "CE#_22") (pintype "unspecified"))
    )
    (net (code "84") (name "{slash}ROMCSB") (class "Default")
      (node (ref "Q1") (pin "2") (pinfunction "B_2") (pintype "unspecified"))
      (node (ref "U1") (pin "24") (pinfunction "IO_C_24") (pintype "bidirectional"))
    )
    (net (code "85") (name "{slash}ROMWR") (class "Default")
      (node (ref "J12") (pin "3") (pinfunction "3_3") (pintype "input"))
      (node (ref "U1") (pin "20") (pinfunction "IO_B_20") (pintype "bidirectional"))
      (node (ref "U2") (pin "31") (pinfunction "WE#_31") (pintype "unspecified"))
    )
    (net (code "86") (name "{slash}WR") (class "Default")
      (node (ref "J1") (pin "24") (pinfunction "/WR_24") (pintype "unspecified"))
      (node (ref "J2") (pin "24") (pinfunction "24_24") (pintype "unspecified"))
      (node (ref "U1") (pin "41") (pinfunction "IO_D_41") (pintype "bidirectional"))
      (node (ref "U3") (pin "29") (pinfunction "WE_29") (pintype "input"))
    )
  )
)
